# PANEL.net
KiCad netlist of a schematic drawn in EAGLE
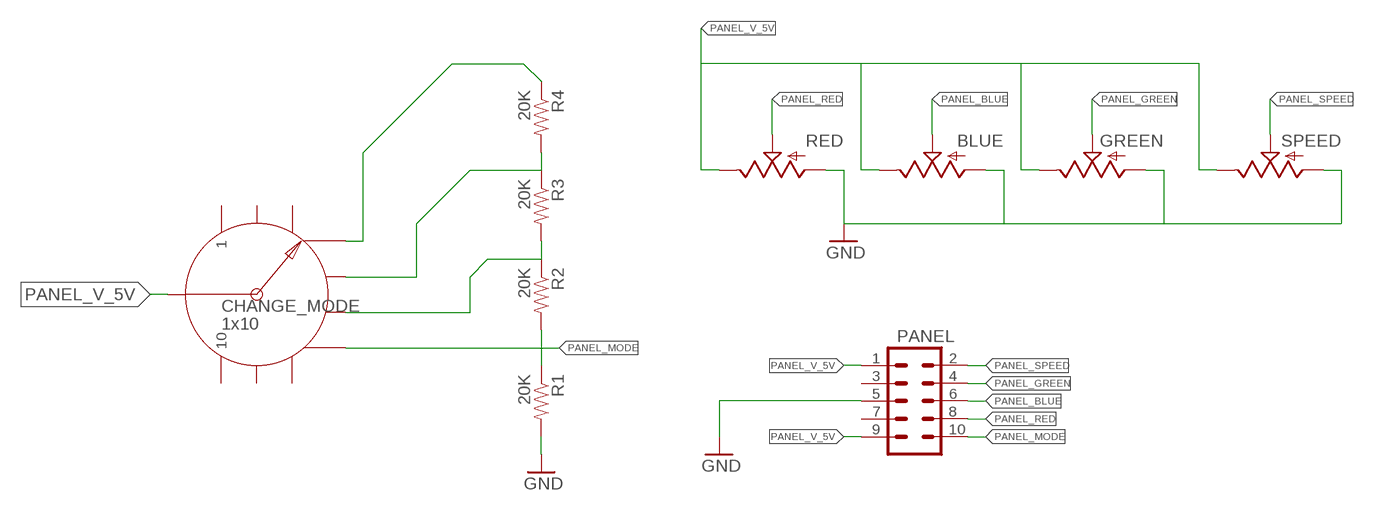
[diagram p0: schematic, sheet 1]

(export (version "E")
  (design (tool "Eeschema 10.0.6"))
  (components
    (comp (ref "BLUE")
      (value "POT-RV16AF-20")
      (footprint "eagle-import:POT_ALPHA_RV16AF-20")
      (libsource (lib "eagle-import") (part "POT-RV16AF-20"))
    )
    (comp (ref "CHANGE_MODE")
      (value "1x10")
      (footprint "eagle-import:ROTARY_SWITCH_1X10")
      (libsource (lib "eagle-import") (part "SWITCH_ROTARY_1X10"))
    )
    (comp (ref "GREEN")
      (value "POT-RV16AF-20")
      (footprint "eagle-import:POT_ALPHA_RV16AF-20")
      (libsource (lib "eagle-import") (part "POT-RV16AF-20"))
    )
    (comp (ref "PANEL")
      (value "M05X2SHD")
      (footprint "eagle-import:2X5-SHROUDED")
      (libsource (lib "eagle-import") (part "M05X2SHD"))
    )
    (comp (ref "R1")
      (value "20K")
      (footprint "eagle-import:1206")
      (libsource (lib "eagle-import") (part "RESISTOR1206"))
    )
    (comp (ref "R2")
      (value "20K")
      (footprint "eagle-import:1206")
      (libsource (lib "eagle-import") (part "RESISTOR1206"))
    )
    (comp (ref "R3")
      (value "20K")
      (footprint "eagle-import:1206")
      (libsource (lib "eagle-import") (part "RESISTOR1206"))
    )
    (comp (ref "R4")
      (value "20K")
      (footprint "eagle-import:1206")
      (libsource (lib "eagle-import") (part "RESISTOR1206"))
    )
    (comp (ref "RED")
      (value "POT-RV16AF-20")
      (footprint "eagle-import:POT_ALPHA_RV16AF-20")
      (libsource (lib "eagle-import") (part "POT-RV16AF-20"))
    )
    (comp (ref "SPEED")
      (value "POT-RV16AF-20")
      (footprint "eagle-import:POT_ALPHA_RV16AF-20")
      (libsource (lib "eagle-import") (part "POT-RV16AF-20"))
    )
  )
  (nets
    (net (code "1") (name "GND") (class "Default")
      (node (ref "BLUE") (pin "1") (pinfunction "A_1") (pintype "passive"))
      (node (ref "GREEN") (pin "1") (pinfunction "A_1") (pintype "passive"))
      (node (ref "PANEL") (pin "5") (pinfunction "5_5") (pintype "passive"))
      (node (ref "R1") (pin "2") (pinfunction "2_2") (pintype "passive"))
      (node (ref "RED") (pin "1") (pinfunction "A_1") (pintype "passive"))
      (node (ref "SPEED") (pin "1") (pinfunction "A_1") (pintype "passive"))
    )
    (net (code "2") (name "Net-(CHANGE_MODE-Pad4)") (class "Default")
      (node (ref "CHANGE_MODE") (pin "4") (pinfunction "4_4") (pintype "bidirectional"))
      (node (ref "R4") (pin "1") (pinfunction "1_1") (pintype "passive"))
    )
    (net (code "3") (name "Net-(CHANGE_MODE-Pad5)") (class "Default")
      (node (ref "CHANGE_MODE") (pin "5") (pinfunction "5_5") (pintype "bidirectional"))
      (node (ref "R3") (pin "1") (pinfunction "1_1") (pintype "passive"))
      (node (ref "R4") (pin "2") (pinfunction "2_2") (pintype "passive"))
    )
    (net (code "4") (name "Net-(CHANGE_MODE-Pad6)") (class "Default")
      (node (ref "CHANGE_MODE") (pin "6") (pinfunction "6_6") (pintype "bidirectional"))
      (node (ref "R2") (pin "1") (pinfunction "1_1") (pintype "passive"))
      (node (ref "R3") (pin "2") (pinfunction "2_2") (pintype "passive"))
    )
    (net (code "5") (name "PANEL_BLUE") (class "Default")
      (node (ref "BLUE") (pin "2") (pinfunction "S_2") (pintype "passive"))
      (node (ref "PANEL") (pin "6") (pinfunction "6_6") (pintype "passive"))
    )
    (net (code "6") (name "PANEL_GREEN") (class "Default")
      (node (ref "GREEN") (pin "2") (pinfunction "S_2") (pintype "passive"))
      (node (ref "PANEL") (pin "4") (pinfunction "4_4") (pintype "passive"))
    )
    (net (code "7") (name "PANEL_MODE") (class "Default")
      (node (ref "CHANGE_MODE") (pin "7") (pinfunction "7_7") (pintype "bidirectional"))
      (node (ref "PANEL") (pin "10") (pinfunction "10_10") (pintype "passive"))
      (node (ref "R1") (pin "1") (pinfunction "1_1") (pintype "passive"))
      (node (ref "R2") (pin "2") (pinfunction "2_2") (pintype "passive"))
    )
    (net (code "8") (name "PANEL_RED") (class "Default")
      (node (ref "PANEL") (pin "8") (pinfunction "8_8") (pintype "passive"))
      (node (ref "RED") (pin "2") (pinfunction "S_2") (pintype "passive"))
    )
    (net (code "9") (name "PANEL_SPEED") (class "Default")
      (node (ref "PANEL") (pin "2") (pinfunction "2_2") (pintype "passive"))
      (node (ref "SPEED") (pin "2") (pinfunction "S_2") (pintype "passive"))
    )
    (net (code "10") (name "PANEL_V_5V") (class "Default")
      (node (ref "BLUE") (pin "3") (pinfunction "E_3") (pintype "passive"))
      (node (ref "CHANGE_MODE") (pin "COMMON") (pinfunction "COMMON_COMMON") (pintype "bidirectional"))
      (node (ref "GREEN") (pin "3") (pinfunction "E_3") (pintype "passive"))
      (node (ref "PANEL") (pin "1") (pinfunction "1_1") (pintype "passive"))
      (node (ref "PANEL") (pin "9") (pinfunction "9_9") (pintype "passive"))
      (node (ref "RED") (pin "3") (pinfunction "E_3") (pintype "passive"))
      (node (ref "SPEED") (pin "3") (pinfunction "E_3") (pintype "passive"))
    )
    (net (code "11") (name "unconnected-(CHANGE_MODE-Pad1)") (class "Default")
      (node (ref "CHANGE_MODE") (pin "1") (pinfunction "1_1") (pintype "bidirectional"))
    )
    (net (code "12") (name "unconnected-(CHANGE_MODE-Pad2)") (class "Default")
      (node (ref "CHANGE_MODE") (pin "2") (pinfunction "2_2") (pintype "bidirectional"))
    )
    (net (code "13") (name "unconnected-(CHANGE_MODE-Pad3)") (class "Default")
      (node (ref "CHANGE_MODE") (pin "3") (pinfunction "3_3") (pintype "bidirectional"))
    )
    (net (code "14") (name "unconnected-(CHANGE_MODE-Pad8)") (class "Default")
      (node (ref "CHANGE_MODE") (pin "8") (pinfunction "8_8") (pintype "bidirectional"))
    )
    (net (code "15") (name "unconnected-(CHANGE_MODE-Pad9)") (class "Default")
      (node (ref "CHANGE_MODE") (pin "9") (pinfunction "9_9") (pintype "bidirectional"))
    )
    (net (code "16") (name "unconnected-(CHANGE_MODE-Pad10)") (class "Default")
      (node (ref "CHANGE_MODE") (pin "10") (pinfunction "10_10") (pintype "bidirectional"))
    )
    (net (code "17") (name "unconnected-(PANEL-Pad3)") (class "Default")
      (node (ref "PANEL") (pin "3") (pinfunction "3_3") (pintype "passive"))
    )
    (net (code "18") (name "unconnected-(PANEL-Pad7)") (class "Default")
      (node (ref "PANEL") (pin "7") (pinfunction "7_7") (pintype "passive"))
    )
  )
)
